# Interface.net
KiCad netlist of a schematic drawn in Altium Designer
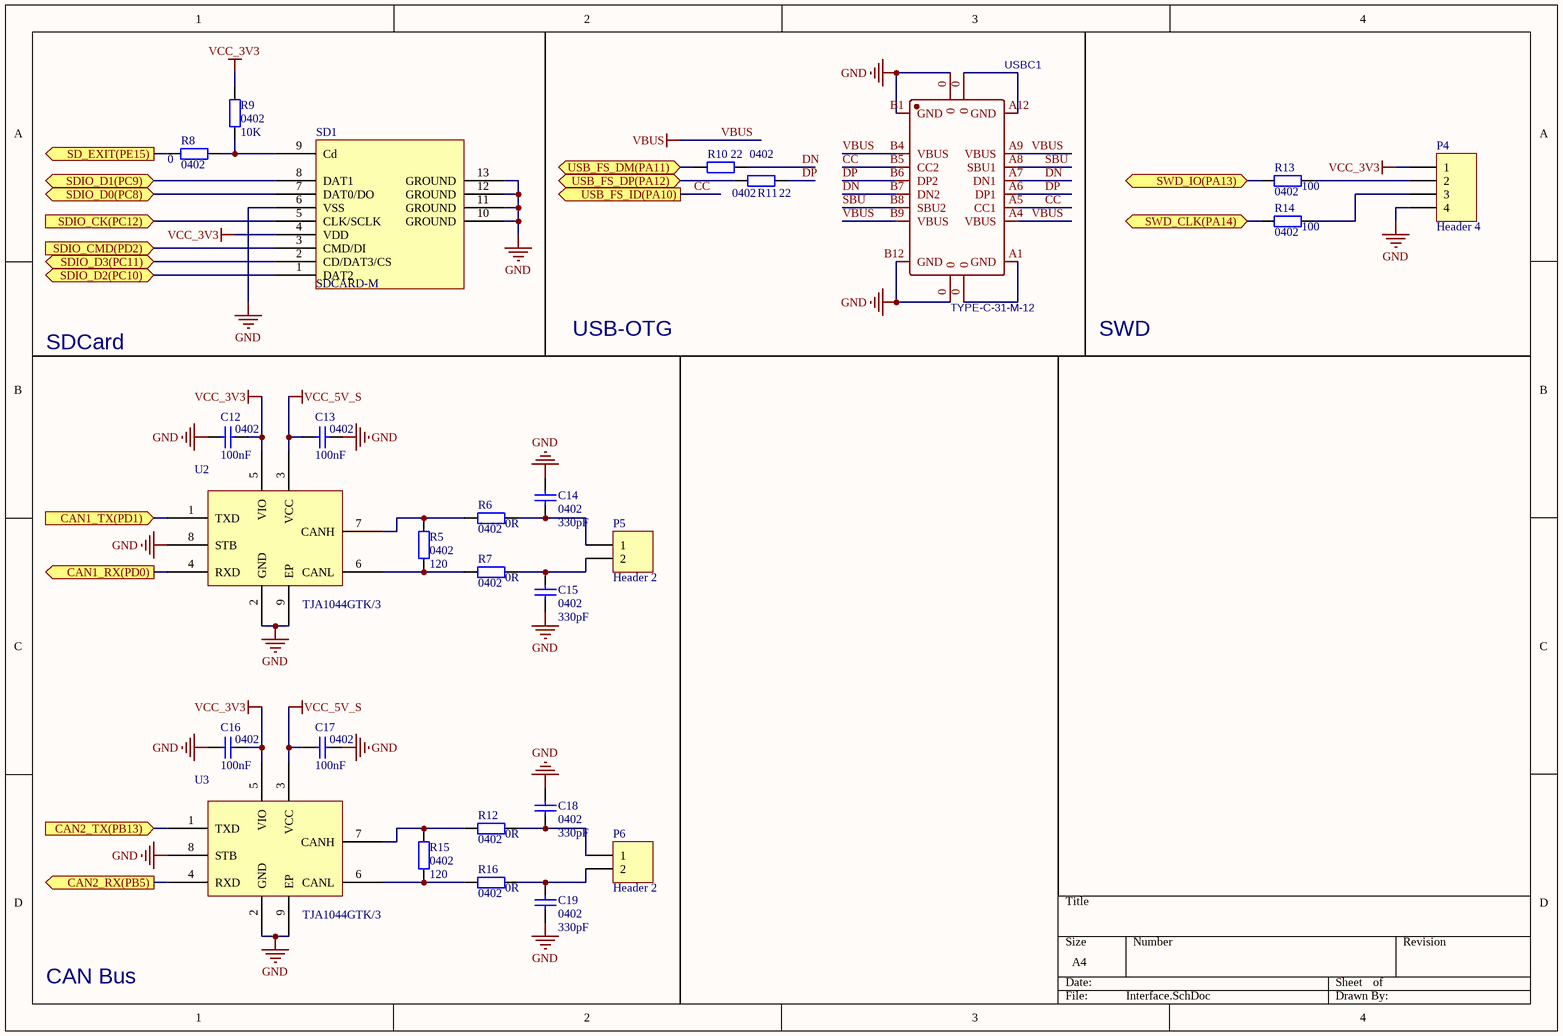
[diagram p0: Interface.SchDoc]

(export (version "E")
  (design (tool "Eeschema 10.0.6"))
  (components
    (comp (ref "C12")
      (value "0402")
      (footprint "C 0402_L")
      (fields (field (name "ALTIUM_VALUE") "100nF"))
      (libsource (lib "QT") (part "CAP"))
    )
    (comp (ref "C13")
      (value "0402")
      (footprint "C 0402_L")
      (fields (field (name "ALTIUM_VALUE") "100nF"))
      (libsource (lib "QT") (part "CAP"))
    )
    (comp (ref "C14")
      (value "0402")
      (footprint "C 0402_L")
      (fields (field (name "ALTIUM_VALUE") "330pF"))
      (libsource (lib "QT") (part "CAP"))
    )
    (comp (ref "C15")
      (value "0402")
      (footprint "C 0402_L")
      (fields (field (name "ALTIUM_VALUE") "330pF"))
      (libsource (lib "QT") (part "CAP"))
    )
    (comp (ref "C16")
      (value "0402")
      (footprint "C 0402_L")
      (fields (field (name "ALTIUM_VALUE") "100nF"))
      (libsource (lib "QT") (part "CAP"))
    )
    (comp (ref "C17")
      (value "0402")
      (footprint "C 0402_L")
      (fields (field (name "ALTIUM_VALUE") "100nF"))
      (libsource (lib "QT") (part "CAP"))
    )
    (comp (ref "C18")
      (value "0402")
      (footprint "C 0402_L")
      (fields (field (name "ALTIUM_VALUE") "330pF"))
      (libsource (lib "QT") (part "CAP"))
    )
    (comp (ref "C19")
      (value "0402")
      (footprint "C 0402_L")
      (fields (field (name "ALTIUM_VALUE") "330pF"))
      (libsource (lib "QT") (part "CAP"))
    )
    (comp (ref "P4")
      (value "Header 4")
      (footprint "HDR2.54-LI-4P")
      (description "Header, 4-Pin")
      (fields (field (name "PUBLISHER") "Altium Limited"))
      (libsource (lib "QT") (part "Header 4"))
    )
    (comp (ref "P5")
      (value "Header 2")
      (footprint "HDR2.54-LI-2P")
      (description "Header, 2-Pin")
      (fields (field (name "PUBLISHER") "Altium Limited"))
      (libsource (lib "QT") (part "Header 2"))
    )
    (comp (ref "P6")
      (value "Header 2")
      (footprint "HDR2.54-LI-2P")
      (description "Header, 2-Pin")
      (fields (field (name "PUBLISHER") "Altium Limited"))
      (libsource (lib "QT") (part "Header 2"))
    )
    (comp (ref "R5")
      (value "0402")
      (footprint "R 0402_L")
      (description "Resistor")
      (fields (field (name "ALTIUM_VALUE") "120") (field (name "PUBLISHER") "Altium Limited"))
      (libsource (lib "QT") (part "RES2"))
    )
    (comp (ref "R6")
      (value "0402")
      (footprint "R 0402_L")
      (description "Resistor")
      (fields (field (name "ALTIUM_VALUE") "0R") (field (name "PUBLISHER") "Altium Limited"))
      (libsource (lib "") (part "RES2_1"))
    )
    (comp (ref "R7")
      (value "0402")
      (footprint "R 0402_L")
      (description "Resistor")
      (fields (field (name "ALTIUM_VALUE") "0R") (field (name "PUBLISHER") "Altium Limited"))
      (libsource (lib "") (part "RES2_1"))
    )
    (comp (ref "R8")
      (value "0402")
      (footprint "R 0402_L")
      (description "Resistor")
      (fields (field (name "ALTIUM_VALUE") "0") (field (name "PUBLISHER") "Altium Limited"))
      (libsource (lib "") (part "RES2_2"))
    )
    (comp (ref "R9")
      (value "0402")
      (footprint "R 0402_L")
      (description "Resistor")
      (fields (field (name "ALTIUM_VALUE") "10K") (field (name "PUBLISHER") "Altium Limited"))
      (libsource (lib "QT") (part "RES2"))
    )
    (comp (ref "R10")
      (value "0402")
      (footprint "R 0402_L")
      (description "Resistor")
      (fields (field (name "ALTIUM_VALUE") "22") (field (name "PUBLISHER") "Altium Limited"))
      (libsource (lib "") (part "RES2_2"))
    )
    (comp (ref "R11")
      (value "0402")
      (footprint "R 0402_L")
      (description "Resistor")
      (fields (field (name "ALTIUM_VALUE") "22") (field (name "PUBLISHER") "Altium Limited"))
      (libsource (lib "") (part "RES2_2"))
    )
    (comp (ref "R12")
      (value "0402")
      (footprint "R 0402_L")
      (description "Resistor")
      (fields (field (name "ALTIUM_VALUE") "0R") (field (name "PUBLISHER") "Altium Limited"))
      (libsource (lib "") (part "RES2_1"))
    )
    (comp (ref "R13")
      (value "0402")
      (footprint "R 0402_L")
      (description "Resistor")
      (fields (field (name "ALTIUM_VALUE") "100") (field (name "PUBLISHER") "Altium Limited"))
      (libsource (lib "") (part "RES2_2"))
    )
    (comp (ref "R14")
      (value "0402")
      (footprint "R 0402_L")
      (description "Resistor")
      (fields (field (name "ALTIUM_VALUE") "100") (field (name "PUBLISHER") "Altium Limited"))
      (libsource (lib "") (part "RES2_2"))
    )
    (comp (ref "R15")
      (value "0402")
      (footprint "R 0402_L")
      (description "Resistor")
      (fields (field (name "ALTIUM_VALUE") "120") (field (name "PUBLISHER") "Altium Limited"))
      (libsource (lib "QT") (part "RES2"))
    )
    (comp (ref "R16")
      (value "0402")
      (footprint "R 0402_L")
      (description "Resistor")
      (fields (field (name "ALTIUM_VALUE") "0R") (field (name "PUBLISHER") "Altium Limited"))
      (libsource (lib "") (part "RES2_1"))
    )
    (comp (ref "SD1")
      (value "SDCARD-M")
      (footprint "SDCARD-M")
      (description "TF卡槽")
      (libsource (lib "Fszhang") (part "SDCARD-M"))
    )
    (comp (ref "U2")
      (value "TJA1044GTK/3")
      (footprint "HVSON8")
      (libsource (lib "常用元件库") (part "TJA1044GTK/3"))
    )
    (comp (ref "U3")
      (value "TJA1044GTK/3")
      (footprint "HVSON8")
      (libsource (lib "常用元件库") (part "TJA1044GTK/3"))
    )
    (comp (ref "USBC1")
      (value "TYPE-C-31-M-12")
      (footprint "USB-TYPE-C_16PIN-MALE-TYPE-C-31-M-12")
      (libsource (lib "Interface") (part "TYPE-C-31-M-12"))
    )
  )
  (nets
    (net (code "1") (name "/CAN1_RX(PD0)") (class "Default")
      (node (ref "U2") (pin "4") (pinfunction "RXD_4") (pintype "passive"))
    )
    (net (code "2") (name "/CAN1_TX(PD1)") (class "Default")
      (node (ref "U2") (pin "1") (pinfunction "TXD_1") (pintype "passive"))
    )
    (net (code "3") (name "/CAN2_RX(PB5)") (class "Default")
      (node (ref "U3") (pin "4") (pinfunction "RXD_4") (pintype "passive"))
    )
    (net (code "4") (name "/CAN2_TX(PB13)") (class "Default")
      (node (ref "U3") (pin "1") (pinfunction "TXD_1") (pintype "passive"))
    )
    (net (code "5") (name "/CC") (class "Default")
      (node (ref "USBC1") (pin "A5") (pinfunction "CC1_A5") (pintype "passive"))
      (node (ref "USBC1") (pin "B5") (pinfunction "CC2_B5") (pintype "passive"))
    )
    (net (code "6") (name "/DN") (class "Default")
      (node (ref "R10") (pin "2") (pinfunction "2_2") (pintype "passive"))
      (node (ref "USBC1") (pin "A7") (pinfunction "DN1_A7") (pintype "passive"))
      (node (ref "USBC1") (pin "B7") (pinfunction "DN2_B7") (pintype "passive"))
    )
    (net (code "7") (name "/DP") (class "Default")
      (node (ref "R11") (pin "2") (pinfunction "2_2") (pintype "passive"))
      (node (ref "USBC1") (pin "A6") (pinfunction "DP1_A6") (pintype "passive"))
      (node (ref "USBC1") (pin "B6") (pinfunction "DP2_B6") (pintype "passive"))
    )
    (net (code "8") (name "/SBU") (class "Default")
      (node (ref "USBC1") (pin "A8") (pinfunction "SBU1_A8") (pintype "passive"))
      (node (ref "USBC1") (pin "B8") (pinfunction "SBU2_B8") (pintype "passive"))
    )
    (net (code "9") (name "/SDIO_CK(PC12)") (class "Default")
      (node (ref "SD1") (pin "5") (pinfunction "CLK/SCLK_5") (pintype "passive"))
    )
    (net (code "10") (name "/SDIO_CMD(PD2)") (class "Default")
      (node (ref "SD1") (pin "3") (pinfunction "CMD/DI_3") (pintype "passive"))
    )
    (net (code "11") (name "/SDIO_D0(PC8)") (class "Default")
      (node (ref "SD1") (pin "7") (pinfunction "DAT0/DO_7") (pintype "passive"))
    )
    (net (code "12") (name "/SDIO_D1(PC9)") (class "Default")
      (node (ref "SD1") (pin "8") (pinfunction "DAT1_8") (pintype "passive"))
    )
    (net (code "13") (name "/SDIO_D2(PC10)") (class "Default")
      (node (ref "SD1") (pin "1") (pinfunction "DAT2_1") (pintype "passive"))
    )
    (net (code "14") (name "/SDIO_D3(PC11)") (class "Default")
      (node (ref "SD1") (pin "2") (pinfunction "CD/DAT3/CS_2") (pintype "passive"))
    )
    (net (code "15") (name "/SD_EXIT(PE15)") (class "Default")
      (node (ref "R8") (pin "1") (pinfunction "1_1") (pintype "passive"))
    )
    (net (code "16") (name "/SWD_CLK(PA14)") (class "Default")
      (node (ref "R14") (pin "1") (pinfunction "1_1") (pintype "passive"))
    )
    (net (code "17") (name "/SWD_IO(PA13)") (class "Default")
      (node (ref "R13") (pin "1") (pinfunction "1_1") (pintype "passive"))
    )
    (net (code "18") (name "/USB_FS_DM(PA11)") (class "Default")
      (node (ref "R10") (pin "1") (pinfunction "1_1") (pintype "passive"))
    )
    (net (code "19") (name "/USB_FS_DP(PA12)") (class "Default")
      (node (ref "R11") (pin "1") (pinfunction "1_1") (pintype "passive"))
    )
    (net (code "20") (name "GND") (class "Default")
      (node (ref "C12") (pin "1") (pinfunction "1_1") (pintype "passive"))
      (node (ref "C13") (pin "2") (pinfunction "2_2") (pintype "passive"))
      (node (ref "C14") (pin "2") (pinfunction "2_2") (pintype "passive"))
      (node (ref "C15") (pin "1") (pinfunction "1_1") (pintype "passive"))
      (node (ref "C16") (pin "1") (pinfunction "1_1") (pintype "passive"))
      (node (ref "C17") (pin "2") (pinfunction "2_2") (pintype "passive"))
      (node (ref "C18") (pin "2") (pinfunction "2_2") (pintype "passive"))
      (node (ref "C19") (pin "1") (pinfunction "1_1") (pintype "passive"))
      (node (ref "P4") (pin "4") (pinfunction "4_4") (pintype "passive"))
      (node (ref "SD1") (pin "10") (pinfunction "GROUND_10") (pintype "passive"))
      (node (ref "SD1") (pin "11") (pinfunction "GROUND_11") (pintype "passive"))
      (node (ref "SD1") (pin "12") (pinfunction "GROUND_12") (pintype "passive"))
      (node (ref "SD1") (pin "13") (pinfunction "GROUND_13") (pintype "passive"))
      (node (ref "SD1") (pin "6") (pinfunction "VSS_6") (pintype "passive"))
      (node (ref "U2") (pin "2") (pinfunction "GND_2") (pintype "passive"))
      (node (ref "U2") (pin "8") (pinfunction "STB_8") (pintype "passive"))
      (node (ref "U2") (pin "9") (pinfunction "EP_9") (pintype "passive"))
      (node (ref "U3") (pin "2") (pinfunction "GND_2") (pintype "passive"))
      (node (ref "U3") (pin "8") (pinfunction "STB_8") (pintype "passive"))
      (node (ref "U3") (pin "9") (pinfunction "EP_9") (pintype "passive"))
      (node (ref "USBC1") (pin "0") (pinfunction "0_0") (pintype "passive"))
      (node (ref "USBC1") (pin "B1") (pinfunction "GND_B1") (pintype "passive"))
      (node (ref "USBC1") (pin "B12") (pinfunction "GND_B12") (pintype "passive"))
    )
    (net (code "21") (name "Net-(C14-Pad1)") (class "Default")
      (node (ref "C14") (pin "1") (pinfunction "1_1") (pintype "passive"))
      (node (ref "P5") (pin "1") (pinfunction "1_1") (pintype "passive"))
      (node (ref "R6") (pin "1") (pinfunction "1_1") (pintype "passive"))
    )
    (net (code "22") (name "Net-(C15-Pad2)") (class "Default")
      (node (ref "C15") (pin "2") (pinfunction "2_2") (pintype "passive"))
      (node (ref "P5") (pin "2") (pinfunction "2_2") (pintype "passive"))
      (node (ref "R7") (pin "1") (pinfunction "1_1") (pintype "passive"))
    )
    (net (code "23") (name "Net-(C18-Pad1)") (class "Default")
      (node (ref "C18") (pin "1") (pinfunction "1_1") (pintype "passive"))
      (node (ref "P6") (pin "1") (pinfunction "1_1") (pintype "passive"))
      (node (ref "R12") (pin "1") (pinfunction "1_1") (pintype "passive"))
    )
    (net (code "24") (name "Net-(C19-Pad2)") (class "Default")
      (node (ref "C19") (pin "2") (pinfunction "2_2") (pintype "passive"))
      (node (ref "P6") (pin "2") (pinfunction "2_2") (pintype "passive"))
      (node (ref "R16") (pin "1") (pinfunction "1_1") (pintype "passive"))
    )
    (net (code "25") (name "Net-(P4-Pad2)") (class "Default")
      (node (ref "P4") (pin "2") (pinfunction "2_2") (pintype "passive"))
      (node (ref "R13") (pin "2") (pinfunction "2_2") (pintype "passive"))
    )
    (net (code "26") (name "Net-(P4-Pad3)") (class "Default")
      (node (ref "P4") (pin "3") (pinfunction "3_3") (pintype "passive"))
      (node (ref "R14") (pin "2") (pinfunction "2_2") (pintype "passive"))
    )
    (net (code "27") (name "Net-(SD1-Cd)") (class "Default")
      (node (ref "R8") (pin "2") (pinfunction "2_2") (pintype "passive"))
      (node (ref "R9") (pin "1") (pinfunction "1_1") (pintype "passive"))
      (node (ref "SD1") (pin "9") (pinfunction "Cd_9") (pintype "passive"))
    )
    (net (code "28") (name "Net-(U2-CANH)") (class "Default")
      (node (ref "R5") (pin "2") (pinfunction "2_2") (pintype "passive"))
      (node (ref "R6") (pin "2") (pinfunction "2_2") (pintype "passive"))
      (node (ref "U2") (pin "7") (pinfunction "CANH_7") (pintype "passive"))
    )
    (net (code "29") (name "Net-(U2-CANL)") (class "Default")
      (node (ref "R5") (pin "1") (pinfunction "1_1") (pintype "passive"))
      (node (ref "R7") (pin "2") (pinfunction "2_2") (pintype "passive"))
      (node (ref "U2") (pin "6") (pinfunction "CANL_6") (pintype "passive"))
    )
    (net (code "30") (name "Net-(U3-CANH)") (class "Default")
      (node (ref "R12") (pin "2") (pinfunction "2_2") (pintype "passive"))
      (node (ref "R15") (pin "2") (pinfunction "2_2") (pintype "passive"))
      (node (ref "U3") (pin "7") (pinfunction "CANH_7") (pintype "passive"))
    )
    (net (code "31") (name "Net-(U3-CANL)") (class "Default")
      (node (ref "R15") (pin "1") (pinfunction "1_1") (pintype "passive"))
      (node (ref "R16") (pin "2") (pinfunction "2_2") (pintype "passive"))
      (node (ref "U3") (pin "6") (pinfunction "CANL_6") (pintype "passive"))
    )
    (net (code "32") (name "Net-(USBC1-GND-PadA1)") (class "Default")
      (node (ref "USBC1") (pin "0") (pinfunction "0_0") (pintype "passive"))
      (node (ref "USBC1") (pin "A1") (pinfunction "GND_A1") (pintype "passive"))
    )
    (net (code "33") (name "Net-(USBC1-GND-PadA12)") (class "Default")
      (node (ref "USBC1") (pin "0") (pinfunction "0_0") (pintype "passive"))
      (node (ref "USBC1") (pin "A12") (pinfunction "GND_A12") (pintype "passive"))
    )
    (net (code "34") (name "VBUS") (class "Default")
      (node (ref "USBC1") (pin "A4") (pinfunction "VBUS_A4") (pintype "passive"))
      (node (ref "USBC1") (pin "A9") (pinfunction "VBUS_A9") (pintype "passive"))
      (node (ref "USBC1") (pin "B4") (pinfunction "VBUS_B4") (pintype "passive"))
      (node (ref "USBC1") (pin "B9") (pinfunction "VBUS_B9") (pintype "passive"))
    )
    (net (code "35") (name "VCC_3V3") (class "Default")
      (node (ref "C12") (pin "2") (pinfunction "2_2") (pintype "passive"))
      (node (ref "C16") (pin "2") (pinfunction "2_2") (pintype "passive"))
      (node (ref "P4") (pin "1") (pinfunction "1_1") (pintype "passive"))
      (node (ref "R9") (pin "2") (pinfunction "2_2") (pintype "passive"))
      (node (ref "SD1") (pin "4") (pinfunction "VDD_4") (pintype "passive"))
      (node (ref "U2") (pin "5") (pinfunction "VIO_5") (pintype "passive"))
      (node (ref "U3") (pin "5") (pinfunction "VIO_5") (pintype "passive"))
    )
    (net (code "36") (name "VCC_5V_S") (class "Default")
      (node (ref "C13") (pin "1") (pinfunction "1_1") (pintype "passive"))
      (node (ref "C17") (pin "1") (pinfunction "1_1") (pintype "passive"))
      (node (ref "U2") (pin "3") (pinfunction "VCC_3") (pintype "passive"))
      (node (ref "U3") (pin "3") (pinfunction "VCC_3") (pintype "passive"))
    )
  )
)
